# Power_Management.net
KiCad netlist of a schematic drawn in Altium Designer
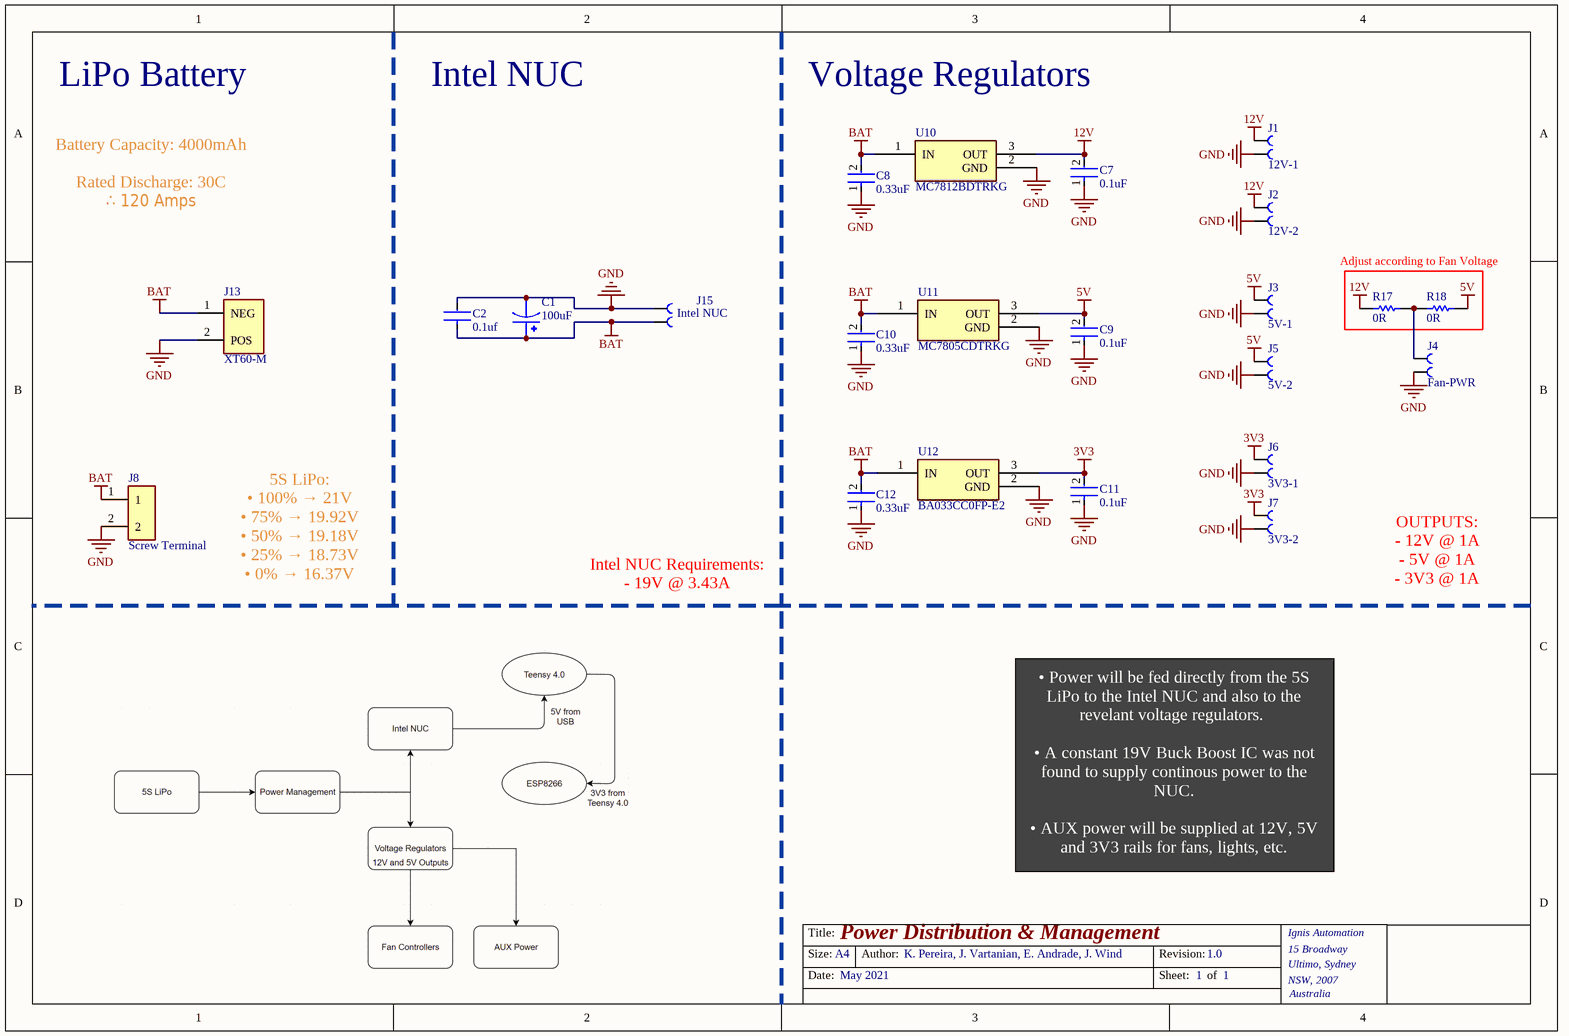
[diagram p0: Power Management.SchDoc]

(export (version "E")
  (design (tool "Eeschema 10.0.6"))
  (components
    (comp (ref "C1")
      (value "100uF")
      (footprint "SnapEDApcb:CAPAE660X800N_EEE-FPV101XAP")
      (description "CAP ALUM 100UF 20% 25V SMD")
      (fields (field (name "PART NUMBER") "EEE-1EA101AP"))
      (libsource (lib "SnapEDAsch") (part "EEE-FPV101XAP"))
    )
    (comp (ref "C2")
      (value "0.1uf")
      (footprint "FP-CL10-IPC_C")
      (description "CAP CER 0.1UF 50V X7R 0603")
      (fields (field (name "PART NUMBER") "1276-CL10B104KB8NNNLCT-ND"))
      (libsource (lib "") (part "b4654b650e69147ec39a6b967a45e02_1"))
    )
    (comp (ref "C7")
      (value "0.1uF")
      (footprint "FP-CL10-IPC_C")
      (description "CAP CER 0.1UF 50V X7R 0603")
      (fields (field (name "PART NUMBER") "1276-CL10B104KB8NNNLCT-ND"))
      (libsource (lib "Altium Content Vault") (part "b4654b650e69147ec39a6b967a45e02"))
    )
    (comp (ref "C8")
      (value "0.33uF")
      (footprint "FP-CL10-IPC_C")
      (description "CAP CER 0.33UF 35V X7R 0603")
      (fields (field (name "PART NUMBER") "CGA3E1X7R1V334K080AC"))
      (libsource (lib "Altium Content Vault") (part "b4654b650e69147ec39a6b967a45e02"))
    )
    (comp (ref "C9")
      (value "0.1uF")
      (footprint "FP-CL10-IPC_C")
      (description "CAP CER 0.1UF 50V X7R 0603")
      (fields (field (name "PART NUMBER") "1276-CL10B104KB8NNNLCT-ND"))
      (libsource (lib "Altium Content Vault") (part "b4654b650e69147ec39a6b967a45e02"))
    )
    (comp (ref "C10")
      (value "0.33uF")
      (footprint "FP-CL10-IPC_C")
      (description "CAP CER 0.33UF 35V X7R 0603")
      (fields (field (name "PART NUMBER") "CGA3E1X7R1V334K080AC"))
      (libsource (lib "Altium Content Vault") (part "b4654b650e69147ec39a6b967a45e02"))
    )
    (comp (ref "C11")
      (value "0.1uF")
      (footprint "FP-CL10-IPC_C")
      (description "CAP CER 0.1UF 50V X7R 0603")
      (fields (field (name "PART NUMBER") "1276-CL10B104KB8NNNLCT-ND"))
      (libsource (lib "Altium Content Vault") (part "b4654b650e69147ec39a6b967a45e02"))
    )
    (comp (ref "C12")
      (value "0.33uF")
      (footprint "FP-CL10-IPC_C")
      (description "CAP CER 0.33UF 35V X7R 0603")
      (fields (field (name "PART NUMBER") "CGA3E1X7R1V334K080AC"))
      (libsource (lib "Altium Content Vault") (part "b4654b650e69147ec39a6b967a45e02"))
    )
    (comp (ref "J1")
      (value "12V-1")
      (footprint "2pin:61300711821")
      (description "2 Pin")
      (libsource (lib "2pin") (part "61300711821"))
    )
    (comp (ref "J2")
      (value "12V-2")
      (footprint "2pin:61300711821")
      (description "2 Pin")
      (libsource (lib "2pin") (part "61300711821"))
    )
    (comp (ref "J3")
      (value "5V-1")
      (footprint "2pin:61300711821")
      (description "2 Pin")
      (libsource (lib "2pin") (part "61300711821"))
    )
    (comp (ref "J4")
      (value "Fan-PWR")
      (footprint "2pin:61300711821")
      (description "2 Pin")
      (libsource (lib "2pin") (part "61300711821"))
    )
    (comp (ref "J5")
      (value "5V-2")
      (footprint "2pin:61300711821")
      (description "2 Pin")
      (libsource (lib "2pin") (part "61300711821"))
    )
    (comp (ref "J6")
      (value "3V3-1")
      (footprint "2pin:61300711821")
      (description "2 Pin")
      (libsource (lib "2pin") (part "61300711821"))
    )
    (comp (ref "J7")
      (value "3V3-2")
      (footprint "2pin:61300711821")
      (description "2 Pin")
      (libsource (lib "2pin") (part "61300711821"))
    )
    (comp (ref "J8")
      (value "Screw Terminal")
      (footprint "OSTTA020161:OST_OSTTA020161")
      (description "2 Position Wire to Board Terminal Block Horizontal with Board 0.197 _5.00mm_ Through Hole")
      (libsource (lib "OSTTA020161") (part "OSTTA020161"))
    )
    (comp (ref "J13")
      (value "XT60-M")
      (footprint "XT60:AMASS_XT60-M")
      (description "XT60")
      (libsource (lib "XT60") (part "XT60-M"))
    )
    (comp (ref "J15")
      (value "Intel NUC")
      (footprint "2pin:61300711821")
      (description "2 Pin")
      (libsource (lib "") (part "61300711821_1"))
    )
    (comp (ref "R17")
      (value "0R")
      (footprint "RESC1608X55X30NL15T15")
      (description "RES 0 OHM JUMPER 1/10W 0603")
      (fields (field (name "PART NUMBER") "RMCF0603ZT0R00TR-ND"))
      (libsource (lib "Altium Content Vault") (part "RES"))
    )
    (comp (ref "R18")
      (value "0R")
      (footprint "RESC1608X55X30NL15T15")
      (description "RES 0 OHM JUMPER 1/10W 0603")
      (fields (field (name "PART NUMBER") "RMCF0603ZT0R00TR-ND"))
      (libsource (lib "Altium Content Vault") (part "RES"))
    )
    (comp (ref "U10")
      (value "MC7812BDTRKG")
      (footprint "DPAK-3_ONS")
      (description "IC REG LINEAR 12V 1A DPAK")
      (fields (field (name "PART NUMBER") "MC7812BDTRKGOSCT-ND"))
      (libsource (lib "12V") (part "MC7812BDTRKG"))
    )
    (comp (ref "U11")
      (value "MC7805CDTRKG")
      (footprint "DPAK-3_ONS")
      (description "IC REG LINEAR 5V 1A DPAK")
      (fields (field (name "PART NUMBER") "MC7805CDTRKGOSCT-ND"))
      (libsource (lib "5V") (part "MC7805CDTRKG"))
    )
    (comp (ref "U12")
      (value "BA033CC0FP-E2")
      (footprint "TO252-3_ROM")
      (description "IC REG LINEAR 3.3V 1A TO252-3")
      (fields (field (name "PART NUMBER") "BA033CC0FP-E2CT-ND"))
      (libsource (lib "3V3") (part "BA033CC0FP-E2"))
    )
  )
  (nets
    (net (code "1") (name "3V3") (class "Default")
      (node (ref "C11") (pin "2") (pinfunction "2_2") (pintype "passive"))
      (node (ref "J6") (pin "2") (pinfunction "2_2") (pintype "passive"))
      (node (ref "J7") (pin "2") (pinfunction "2_2") (pintype "passive"))
      (node (ref "U12") (pin "3") (pinfunction "OUT_3") (pintype "passive"))
    )
    (net (code "2") (name "5V") (class "Default")
      (node (ref "C9") (pin "2") (pinfunction "2_2") (pintype "passive"))
      (node (ref "J3") (pin "2") (pinfunction "2_2") (pintype "passive"))
      (node (ref "J5") (pin "2") (pinfunction "2_2") (pintype "passive"))
      (node (ref "R18") (pin "2") (pinfunction "2_2") (pintype "passive"))
      (node (ref "U11") (pin "3") (pinfunction "OUT_3") (pintype "passive"))
    )
    (net (code "3") (name "12V") (class "Default")
      (node (ref "C7") (pin "2") (pinfunction "2_2") (pintype "passive"))
      (node (ref "J1") (pin "2") (pinfunction "2_2") (pintype "passive"))
      (node (ref "J2") (pin "2") (pinfunction "2_2") (pintype "passive"))
      (node (ref "R17") (pin "1") (pinfunction "1_1") (pintype "passive"))
      (node (ref "U10") (pin "3") (pinfunction "OUT_3") (pintype "passive"))
    )
    (net (code "4") (name "BAT") (class "Default")
      (node (ref "C1") (pin "1") (pinfunction "1_1") (pintype "passive"))
      (node (ref "C10") (pin "2") (pinfunction "2_2") (pintype "passive"))
      (node (ref "C12") (pin "2") (pinfunction "2_2") (pintype "passive"))
      (node (ref "C2") (pin "1") (pinfunction "1_1") (pintype "passive"))
      (node (ref "C8") (pin "2") (pinfunction "2_2") (pintype "passive"))
      (node (ref "J13") (pin "1") (pinfunction "NEG_1") (pintype "passive"))
      (node (ref "J15") (pin "2") (pinfunction "2_2") (pintype "passive"))
      (node (ref "J8") (pin "1") (pinfunction "1_1") (pintype "passive"))
      (node (ref "U10") (pin "1") (pinfunction "IN_1") (pintype "passive"))
      (node (ref "U11") (pin "1") (pinfunction "IN_1") (pintype "passive"))
      (node (ref "U12") (pin "1") (pinfunction "IN_1") (pintype "passive"))
    )
    (net (code "5") (name "GND") (class "Default")
      (node (ref "C1") (pin "2") (pinfunction "2_2") (pintype "passive"))
      (node (ref "C10") (pin "1") (pinfunction "1_1") (pintype "passive"))
      (node (ref "C11") (pin "1") (pinfunction "1_1") (pintype "passive"))
      (node (ref "C12") (pin "1") (pinfunction "1_1") (pintype "passive"))
      (node (ref "C2") (pin "2") (pinfunction "2_2") (pintype "passive"))
      (node (ref "C7") (pin "1") (pinfunction "1_1") (pintype "passive"))
      (node (ref "C8") (pin "1") (pinfunction "1_1") (pintype "passive"))
      (node (ref "C9") (pin "1") (pinfunction "1_1") (pintype "passive"))
      (node (ref "J1") (pin "1") (pinfunction "1_1") (pintype "passive"))
      (node (ref "J13") (pin "2") (pinfunction "POS_2") (pintype "passive"))
      (node (ref "J15") (pin "1") (pinfunction "1_1") (pintype "passive"))
      (node (ref "J2") (pin "1") (pinfunction "1_1") (pintype "passive"))
      (node (ref "J3") (pin "1") (pinfunction "1_1") (pintype "passive"))
      (node (ref "J4") (pin "1") (pinfunction "1_1") (pintype "passive"))
      (node (ref "J5") (pin "1") (pinfunction "1_1") (pintype "passive"))
      (node (ref "J6") (pin "1") (pinfunction "1_1") (pintype "passive"))
      (node (ref "J7") (pin "1") (pinfunction "1_1") (pintype "passive"))
      (node (ref "J8") (pin "2") (pinfunction "2_2") (pintype "passive"))
      (node (ref "U10") (pin "2") (pinfunction "GND_2") (pintype "passive"))
      (node (ref "U11") (pin "2") (pinfunction "GND_2") (pintype "passive"))
      (node (ref "U12") (pin "2") (pinfunction "GND_2") (pintype "passive"))
    )
    (net (code "6") (name "Net-(J4-Pad2)") (class "Default")
      (node (ref "J4") (pin "2") (pinfunction "2_2") (pintype "passive"))
      (node (ref "R17") (pin "2") (pinfunction "2_2") (pintype "passive"))
      (node (ref "R18") (pin "1") (pinfunction "1_1") (pintype "passive"))
    )
  )
)
